# 6-Connectors.net
KiCad netlist of a schematic drawn in Altium Designer
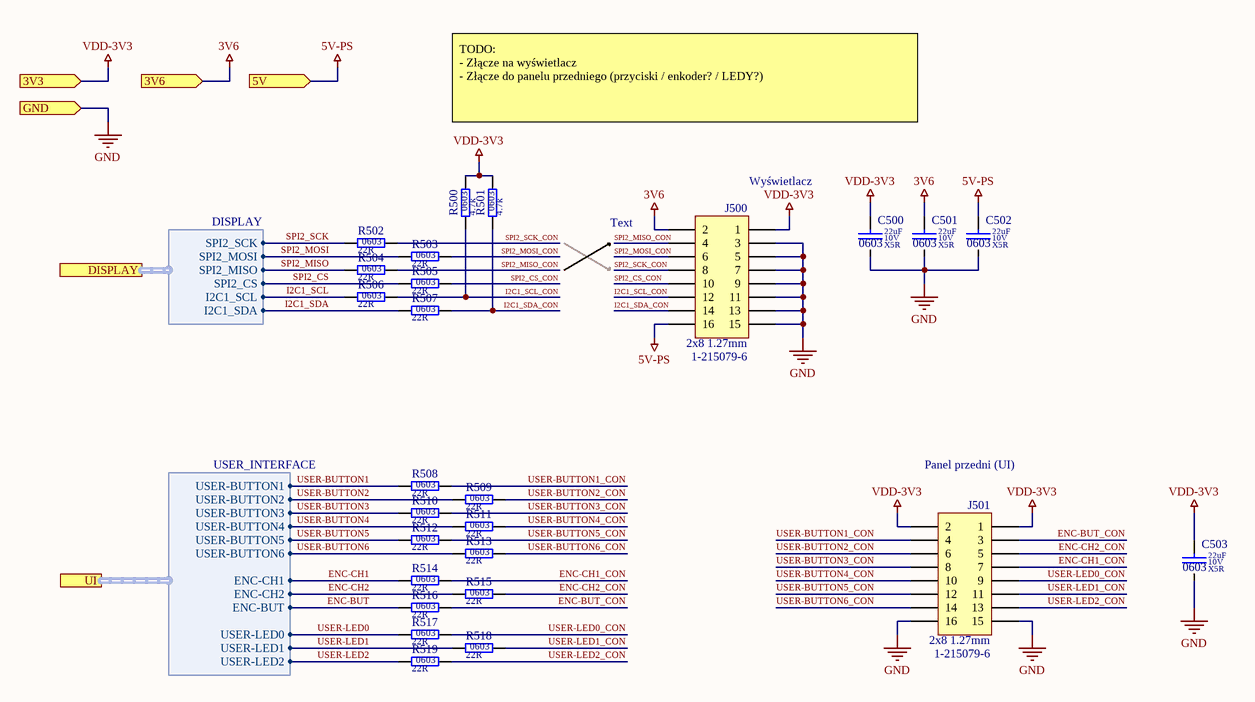
[diagram p0: 6-Connectors.SchDoc]

(export (version "E")
  (design (tool "Eeschema 10.0.6"))
  (components
    (comp (ref "C500")
      (value "22uF")
      (footprint "C_0603_1608")
      (description "Capacitor")
      (fields
        (field (name "DIELECTRIC") "X5R")
        (field (name "VOLTAGE") "10V")
        (field (name "SCH_FOOTPRINT") "0603")
        (field (name "PART NUMBER") "C_22uF_10V_X5R_0603_20")
        (field (name "MANUFACTURER") "Murata")
      )
      (libsource (lib "Library") (part "C"))
    )
    (comp (ref "C501")
      (value "22uF")
      (footprint "C_0603_1608")
      (description "Capacitor")
      (fields
        (field (name "DIELECTRIC") "X5R")
        (field (name "VOLTAGE") "10V")
        (field (name "SCH_FOOTPRINT") "0603")
        (field (name "PART NUMBER") "C_22uF_10V_X5R_0603_20")
        (field (name "MANUFACTURER") "Murata")
      )
      (libsource (lib "Library") (part "C"))
    )
    (comp (ref "C502")
      (value "22uF")
      (footprint "C_0603_1608")
      (description "Capacitor")
      (fields
        (field (name "DIELECTRIC") "X5R")
        (field (name "VOLTAGE") "10V")
        (field (name "SCH_FOOTPRINT") "0603")
        (field (name "PART NUMBER") "C_22uF_10V_X5R_0603_20")
        (field (name "MANUFACTURER") "Murata")
      )
      (libsource (lib "Library") (part "C"))
    )
    (comp (ref "C503")
      (value "22uF")
      (footprint "C_0603_1608")
      (description "Capacitor")
      (fields
        (field (name "DIELECTRIC") "X5R")
        (field (name "VOLTAGE") "10V")
        (field (name "SCH_FOOTPRINT") "0603")
        (field (name "PART NUMBER") "C_22uF_10V_X5R_0603_20")
        (field (name "MANUFACTURER") "Murata")
      )
      (libsource (lib "Library") (part "C"))
    )
    (comp (ref "J500")
      (value "1-215079-6")
      (footprint "J_Micro-Match_2x8_THT")
      (description "Pin Header")
      (fields
        (field (name "SCH_FOOTPRINT") "2x8 1.27mm")
        (field (name "PART NUMBER") "J_Micro-Match_2x8_THT")
        (field (name "MANUFACTURER") "TE Connectivity")
      )
      (libsource (lib "Library") (part "J_HEADER_2x8"))
    )
    (comp (ref "J501")
      (value "1-215079-6")
      (footprint "J_Micro-Match_2x8_THT")
      (description "Pin Header")
      (fields
        (field (name "SCH_FOOTPRINT") "2x8 1.27mm")
        (field (name "PART NUMBER") "J_Micro-Match_2x8_THT")
        (field (name "MANUFACTURER") "TE Connectivity")
      )
      (libsource (lib "Library") (part "J_HEADER_2x8"))
    )
    (comp (ref "R500")
      (value "4.7k")
      (footprint "R_0603_1608")
      (fields
        (field (name "SCH_FOOTPRINT") "0603")
        (field (name "PART NUMBER") "R_4.7k_0603_1")
        (field (name "VOLTAGE") "75V")
        (field (name "POWER") "100mW")
      )
      (libsource (lib "Library") (part "R"))
    )
    (comp (ref "R501")
      (value "4.7k")
      (footprint "R_0603_1608")
      (fields
        (field (name "SCH_FOOTPRINT") "0603")
        (field (name "PART NUMBER") "R_4.7k_0603_1")
        (field (name "VOLTAGE") "75V")
        (field (name "POWER") "100mW")
      )
      (libsource (lib "Library") (part "R"))
    )
    (comp (ref "R502")
      (value "22R")
      (footprint "R_0603_1608")
      (fields
        (field (name "SCH_FOOTPRINT") "0603")
        (field (name "PART NUMBER") "R_22R_0603_5")
        (field (name "VOLTAGE") "50V")
        (field (name "POWER") "125mW")
      )
      (libsource (lib "Library") (part "R"))
    )
    (comp (ref "R503")
      (value "22R")
      (footprint "R_0603_1608")
      (fields
        (field (name "SCH_FOOTPRINT") "0603")
        (field (name "PART NUMBER") "R_22R_0603_5")
        (field (name "VOLTAGE") "50V")
        (field (name "POWER") "125mW")
      )
      (libsource (lib "Library") (part "R"))
    )
    (comp (ref "R504")
      (value "22R")
      (footprint "R_0603_1608")
      (fields
        (field (name "SCH_FOOTPRINT") "0603")
        (field (name "PART NUMBER") "R_22R_0603_5")
        (field (name "VOLTAGE") "50V")
        (field (name "POWER") "125mW")
      )
      (libsource (lib "Library") (part "R"))
    )
    (comp (ref "R505")
      (value "22R")
      (footprint "R_0603_1608")
      (fields
        (field (name "SCH_FOOTPRINT") "0603")
        (field (name "PART NUMBER") "R_22R_0603_5")
        (field (name "VOLTAGE") "50V")
        (field (name "POWER") "125mW")
      )
      (libsource (lib "Library") (part "R"))
    )
    (comp (ref "R506")
      (value "22R")
      (footprint "R_0603_1608")
      (fields
        (field (name "SCH_FOOTPRINT") "0603")
        (field (name "PART NUMBER") "R_22R_0603_5")
        (field (name "VOLTAGE") "50V")
        (field (name "POWER") "125mW")
      )
      (libsource (lib "Library") (part "R"))
    )
    (comp (ref "R507")
      (value "22R")
      (footprint "R_0603_1608")
      (fields
        (field (name "SCH_FOOTPRINT") "0603")
        (field (name "PART NUMBER") "R_22R_0603_5")
        (field (name "VOLTAGE") "50V")
        (field (name "POWER") "125mW")
      )
      (libsource (lib "Library") (part "R"))
    )
    (comp (ref "R508")
      (value "22R")
      (footprint "R_0603_1608")
      (fields
        (field (name "SCH_FOOTPRINT") "0603")
        (field (name "PART NUMBER") "R_22R_0603_5")
        (field (name "VOLTAGE") "50V")
        (field (name "POWER") "125mW")
      )
      (libsource (lib "Library") (part "R"))
    )
    (comp (ref "R509")
      (value "22R")
      (footprint "R_0603_1608")
      (fields
        (field (name "SCH_FOOTPRINT") "0603")
        (field (name "PART NUMBER") "R_22R_0603_5")
        (field (name "VOLTAGE") "50V")
        (field (name "POWER") "125mW")
      )
      (libsource (lib "Library") (part "R"))
    )
    (comp (ref "R510")
      (value "22R")
      (footprint "R_0603_1608")
      (fields
        (field (name "SCH_FOOTPRINT") "0603")
        (field (name "PART NUMBER") "R_22R_0603_5")
        (field (name "VOLTAGE") "50V")
        (field (name "POWER") "125mW")
      )
      (libsource (lib "Library") (part "R"))
    )
    (comp (ref "R511")
      (value "22R")
      (footprint "R_0603_1608")
      (fields
        (field (name "SCH_FOOTPRINT") "0603")
        (field (name "PART NUMBER") "R_22R_0603_5")
        (field (name "VOLTAGE") "50V")
        (field (name "POWER") "125mW")
      )
      (libsource (lib "Library") (part "R"))
    )
    (comp (ref "R512")
      (value "22R")
      (footprint "R_0603_1608")
      (fields
        (field (name "SCH_FOOTPRINT") "0603")
        (field (name "PART NUMBER") "R_22R_0603_5")
        (field (name "VOLTAGE") "50V")
        (field (name "POWER") "125mW")
      )
      (libsource (lib "Library") (part "R"))
    )
    (comp (ref "R513")
      (value "22R")
      (footprint "R_0603_1608")
      (fields
        (field (name "SCH_FOOTPRINT") "0603")
        (field (name "PART NUMBER") "R_22R_0603_5")
        (field (name "VOLTAGE") "50V")
        (field (name "POWER") "125mW")
      )
      (libsource (lib "Library") (part "R"))
    )
    (comp (ref "R514")
      (value "22R")
      (footprint "R_0603_1608")
      (fields
        (field (name "SCH_FOOTPRINT") "0603")
        (field (name "PART NUMBER") "R_22R_0603_5")
        (field (name "VOLTAGE") "50V")
        (field (name "POWER") "125mW")
      )
      (libsource (lib "Library") (part "R"))
    )
    (comp (ref "R515")
      (value "22R")
      (footprint "R_0603_1608")
      (fields
        (field (name "SCH_FOOTPRINT") "0603")
        (field (name "PART NUMBER") "R_22R_0603_5")
        (field (name "VOLTAGE") "50V")
        (field (name "POWER") "125mW")
      )
      (libsource (lib "Library") (part "R"))
    )
    (comp (ref "R516")
      (value "22R")
      (footprint "R_0603_1608")
      (fields
        (field (name "SCH_FOOTPRINT") "0603")
        (field (name "PART NUMBER") "R_22R_0603_5")
        (field (name "VOLTAGE") "50V")
        (field (name "POWER") "125mW")
      )
      (libsource (lib "Library") (part "R"))
    )
    (comp (ref "R517")
      (value "22R")
      (footprint "R_0603_1608")
      (fields
        (field (name "SCH_FOOTPRINT") "0603")
        (field (name "PART NUMBER") "R_22R_0603_5")
        (field (name "VOLTAGE") "50V")
        (field (name "POWER") "125mW")
      )
      (libsource (lib "Library") (part "R"))
    )
    (comp (ref "R518")
      (value "22R")
      (footprint "R_0603_1608")
      (fields
        (field (name "SCH_FOOTPRINT") "0603")
        (field (name "PART NUMBER") "R_22R_0603_5")
        (field (name "VOLTAGE") "50V")
        (field (name "POWER") "125mW")
      )
      (libsource (lib "Library") (part "R"))
    )
    (comp (ref "R519")
      (value "22R")
      (footprint "R_0603_1608")
      (fields
        (field (name "SCH_FOOTPRINT") "0603")
        (field (name "PART NUMBER") "R_22R_0603_5")
        (field (name "VOLTAGE") "50V")
        (field (name "POWER") "125mW")
      )
      (libsource (lib "Library") (part "R"))
    )
  )
  (nets
    (net (code "3") (name "/ENC-BUT") (class "Default")
      (node (ref "R516") (pin "1") (pinfunction "1_1") (pintype "passive"))
    )
    (net (code "4") (name "/ENC-BUT_CON") (class "Default")
      (node (ref "J501") (pin "3") (pinfunction "3_3") (pintype "passive"))
      (node (ref "R516") (pin "2") (pinfunction "2_2") (pintype "passive"))
    )
    (net (code "5") (name "/ENC-CH1") (class "Default")
      (node (ref "R514") (pin "1") (pinfunction "1_1") (pintype "passive"))
    )
    (net (code "6") (name "/ENC-CH1_CON") (class "Default")
      (node (ref "J501") (pin "7") (pinfunction "7_7") (pintype "passive"))
      (node (ref "R514") (pin "2") (pinfunction "2_2") (pintype "passive"))
    )
    (net (code "7") (name "/ENC-CH2") (class "Default")
      (node (ref "R515") (pin "1") (pinfunction "1_1") (pintype "passive"))
    )
    (net (code "8") (name "/ENC-CH2_CON") (class "Default")
      (node (ref "J501") (pin "5") (pinfunction "5_5") (pintype "passive"))
      (node (ref "R515") (pin "2") (pinfunction "2_2") (pintype "passive"))
    )
    (net (code "9") (name "/I2C1_SCL") (class "Default")
      (node (ref "R506") (pin "1") (pinfunction "1_1") (pintype "passive"))
    )
    (net (code "10") (name "/I2C1_SCL_CON") (class "Default")
      (node (ref "J500") (pin "12") (pinfunction "12_12") (pintype "passive"))
      (node (ref "R500") (pin "1") (pinfunction "1_1") (pintype "passive"))
      (node (ref "R506") (pin "2") (pinfunction "2_2") (pintype "passive"))
    )
    (net (code "11") (name "/I2C1_SDA") (class "Default")
      (node (ref "R507") (pin "1") (pinfunction "1_1") (pintype "passive"))
    )
    (net (code "12") (name "/I2C1_SDA_CON") (class "Default")
      (node (ref "J500") (pin "14") (pinfunction "14_14") (pintype "passive"))
      (node (ref "R501") (pin "1") (pinfunction "1_1") (pintype "passive"))
      (node (ref "R507") (pin "2") (pinfunction "2_2") (pintype "passive"))
    )
    (net (code "13") (name "/SPI2_CS") (class "Default")
      (node (ref "R505") (pin "1") (pinfunction "1_1") (pintype "passive"))
    )
    (net (code "14") (name "/SPI2_CS_CON") (class "Default")
      (node (ref "J500") (pin "10") (pinfunction "10_10") (pintype "passive"))
      (node (ref "R505") (pin "2") (pinfunction "2_2") (pintype "passive"))
    )
    (net (code "15") (name "/SPI2_MISO") (class "Default")
      (node (ref "R504") (pin "1") (pinfunction "1_1") (pintype "passive"))
    )
    (net (code "16") (name "/SPI2_MISO_CON") (class "Default")
      (node (ref "J500") (pin "4") (pinfunction "4_4") (pintype "passive"))
      (node (ref "R504") (pin "2") (pinfunction "2_2") (pintype "passive"))
    )
    (net (code "17") (name "/SPI2_MOSI") (class "Default")
      (node (ref "R503") (pin "1") (pinfunction "1_1") (pintype "passive"))
    )
    (net (code "18") (name "/SPI2_MOSI_CON") (class "Default")
      (node (ref "J500") (pin "6") (pinfunction "6_6") (pintype "passive"))
      (node (ref "R503") (pin "2") (pinfunction "2_2") (pintype "passive"))
    )
    (net (code "19") (name "/SPI2_SCK") (class "Default")
      (node (ref "R502") (pin "1") (pinfunction "1_1") (pintype "passive"))
    )
    (net (code "20") (name "/SPI2_SCK_CON") (class "Default")
      (node (ref "J500") (pin "8") (pinfunction "8_8") (pintype "passive"))
      (node (ref "R502") (pin "2") (pinfunction "2_2") (pintype "passive"))
    )
    (net (code "21") (name "/USER-BUTTON1") (class "Default")
      (node (ref "R508") (pin "1") (pinfunction "1_1") (pintype "passive"))
    )
    (net (code "22") (name "/USER-BUTTON1_CON") (class "Default")
      (node (ref "J501") (pin "4") (pinfunction "4_4") (pintype "passive"))
      (node (ref "R508") (pin "2") (pinfunction "2_2") (pintype "passive"))
    )
    (net (code "23") (name "/USER-BUTTON2") (class "Default")
      (node (ref "R509") (pin "1") (pinfunction "1_1") (pintype "passive"))
    )
    (net (code "24") (name "/USER-BUTTON2_CON") (class "Default")
      (node (ref "J501") (pin "6") (pinfunction "6_6") (pintype "passive"))
      (node (ref "R509") (pin "2") (pinfunction "2_2") (pintype "passive"))
    )
    (net (code "25") (name "/USER-BUTTON3") (class "Default")
      (node (ref "R510") (pin "1") (pinfunction "1_1") (pintype "passive"))
    )
    (net (code "26") (name "/USER-BUTTON3_CON") (class "Default")
      (node (ref "J501") (pin "8") (pinfunction "8_8") (pintype "passive"))
      (node (ref "R510") (pin "2") (pinfunction "2_2") (pintype "passive"))
    )
    (net (code "27") (name "/USER-BUTTON4") (class "Default")
      (node (ref "R511") (pin "1") (pinfunction "1_1") (pintype "passive"))
    )
    (net (code "28") (name "/USER-BUTTON4_CON") (class "Default")
      (node (ref "J501") (pin "10") (pinfunction "10_10") (pintype "passive"))
      (node (ref "R511") (pin "2") (pinfunction "2_2") (pintype "passive"))
    )
    (net (code "29") (name "/USER-BUTTON5") (class "Default")
      (node (ref "R512") (pin "1") (pinfunction "1_1") (pintype "passive"))
    )
    (net (code "30") (name "/USER-BUTTON5_CON") (class "Default")
      (node (ref "J501") (pin "12") (pinfunction "12_12") (pintype "passive"))
      (node (ref "R512") (pin "2") (pinfunction "2_2") (pintype "passive"))
    )
    (net (code "31") (name "/USER-BUTTON6") (class "Default")
      (node (ref "R513") (pin "1") (pinfunction "1_1") (pintype "passive"))
    )
    (net (code "32") (name "/USER-BUTTON6_CON") (class "Default")
      (node (ref "J501") (pin "14") (pinfunction "14_14") (pintype "passive"))
      (node (ref "R513") (pin "2") (pinfunction "2_2") (pintype "passive"))
    )
    (net (code "33") (name "/USER-LED0") (class "Default")
      (node (ref "R517") (pin "1") (pinfunction "1_1") (pintype "passive"))
    )
    (net (code "34") (name "/USER-LED0_CON") (class "Default")
      (node (ref "J501") (pin "9") (pinfunction "9_9") (pintype "passive"))
      (node (ref "R517") (pin "2") (pinfunction "2_2") (pintype "passive"))
    )
    (net (code "35") (name "/USER-LED1") (class "Default")
      (node (ref "R518") (pin "1") (pinfunction "1_1") (pintype "passive"))
    )
    (net (code "36") (name "/USER-LED1_CON") (class "Default")
      (node (ref "J501") (pin "11") (pinfunction "11_11") (pintype "passive"))
      (node (ref "R518") (pin "2") (pinfunction "2_2") (pintype "passive"))
    )
    (net (code "37") (name "/USER-LED2") (class "Default")
      (node (ref "R519") (pin "1") (pinfunction "1_1") (pintype "passive"))
    )
    (net (code "38") (name "/USER-LED2_CON") (class "Default")
      (node (ref "J501") (pin "13") (pinfunction "13_13") (pintype "passive"))
      (node (ref "R519") (pin "2") (pinfunction "2_2") (pintype "passive"))
    )
    (net (code "41") (name "3V6") (class "Default")
      (node (ref "C501") (pin "1") (pinfunction "1_1") (pintype "passive"))
      (node (ref "J500") (pin "2") (pinfunction "2_2") (pintype "passive"))
    )
    (net (code "42") (name "5V-PS") (class "Default")
      (node (ref "C502") (pin "1") (pinfunction "1_1") (pintype "passive"))
      (node (ref "J500") (pin "16") (pinfunction "16_16") (pintype "passive"))
    )
    (net (code "43") (name "GND") (class "Default")
      (node (ref "C500") (pin "2") (pinfunction "2_2") (pintype "passive"))
      (node (ref "C501") (pin "2") (pinfunction "2_2") (pintype "passive"))
      (node (ref "C502") (pin "2") (pinfunction "2_2") (pintype "passive"))
      (node (ref "C503") (pin "2") (pinfunction "2_2") (pintype "passive"))
      (node (ref "J500") (pin "11") (pinfunction "11_11") (pintype "passive"))
      (node (ref "J500") (pin "13") (pinfunction "13_13") (pintype "passive"))
      (node (ref "J500") (pin "15") (pinfunction "15_15") (pintype "passive"))
      (node (ref "J500") (pin "3") (pinfunction "3_3") (pintype "passive"))
      (node (ref "J500") (pin "5") (pinfunction "5_5") (pintype "passive"))
      (node (ref "J500") (pin "7") (pinfunction "7_7") (pintype "passive"))
      (node (ref "J500") (pin "9") (pinfunction "9_9") (pintype "passive"))
      (node (ref "J501") (pin "15") (pinfunction "15_15") (pintype "passive"))
      (node (ref "J501") (pin "16") (pinfunction "16_16") (pintype "passive"))
    )
    (net (code "44") (name "VDD-3V3") (class "Default")
      (node (ref "C500") (pin "1") (pinfunction "1_1") (pintype "passive"))
      (node (ref "C503") (pin "1") (pinfunction "1_1") (pintype "passive"))
      (node (ref "J500") (pin "1") (pinfunction "1_1") (pintype "passive"))
      (node (ref "J501") (pin "1") (pinfunction "1_1") (pintype "passive"))
      (node (ref "J501") (pin "2") (pinfunction "2_2") (pintype "passive"))
      (node (ref "R500") (pin "2") (pinfunction "2_2") (pintype "passive"))
      (node (ref "R501") (pin "2") (pinfunction "2_2") (pintype "passive"))
    )
  )
)
